# lumy.net
KiCad netlist of a schematic drawn in EAGLE
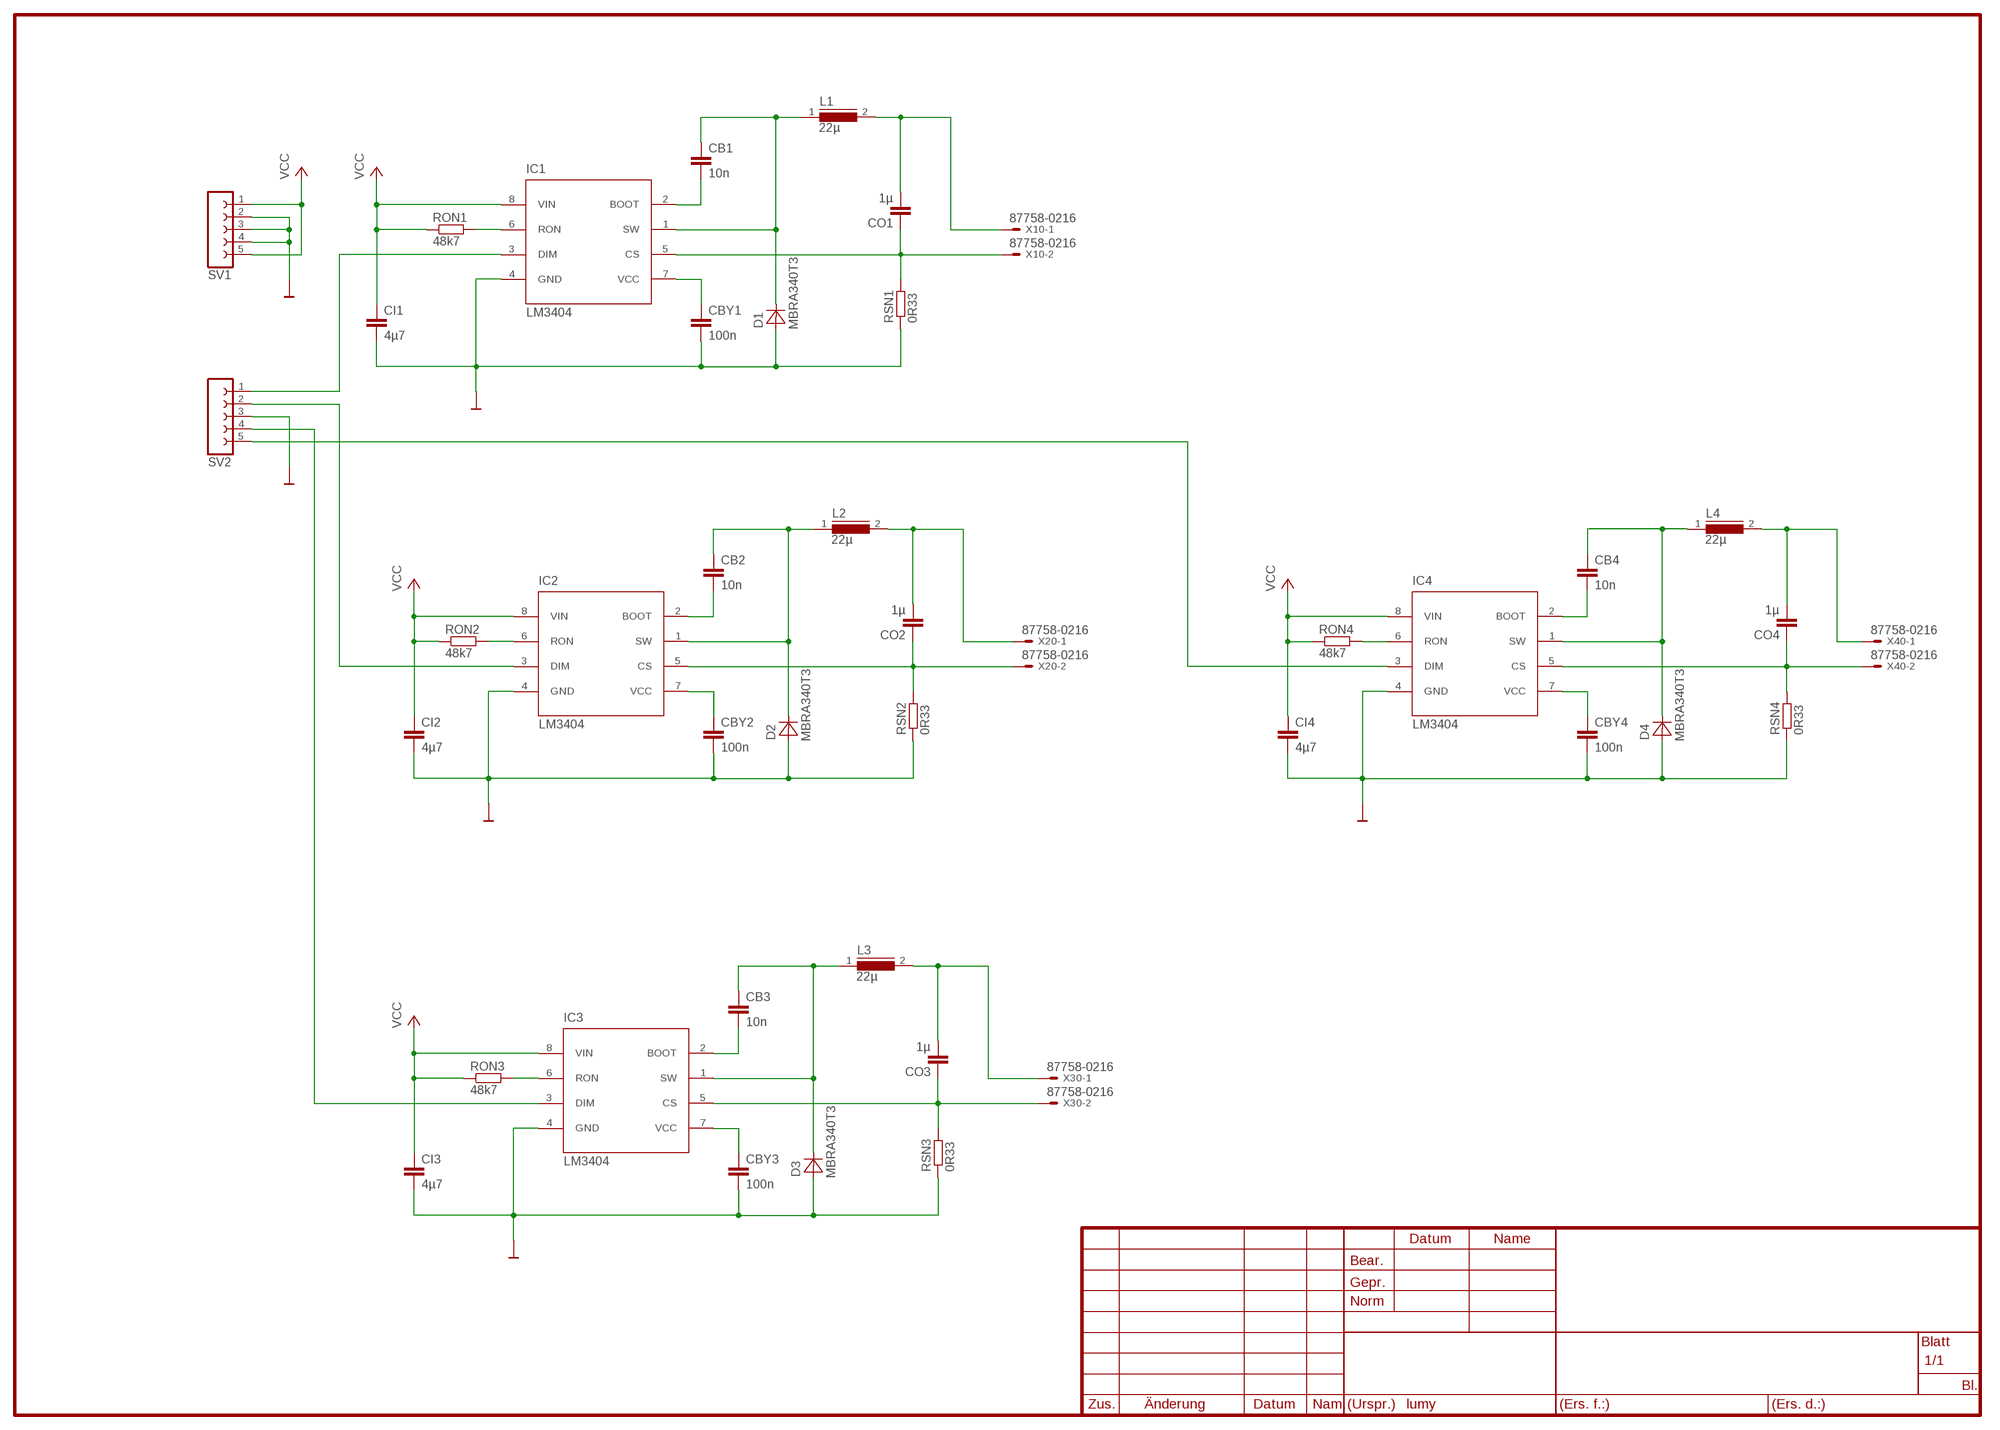
[diagram p0: schematic, sheet 1]

(export (version "E")
  (design (tool "Eeschema 10.0.6"))
  (components
    (comp (ref "CB1")
      (value "10n")
      (footprint "eagle-import:C0603")
      (libsource (lib "eagle-import") (part "C-EUC0603"))
    )
    (comp (ref "CB2")
      (value "10n")
      (footprint "eagle-import:C0603")
      (libsource (lib "eagle-import") (part "C-EUC0603"))
    )
    (comp (ref "CB3")
      (value "10n")
      (footprint "eagle-import:C0603")
      (libsource (lib "eagle-import") (part "C-EUC0603"))
    )
    (comp (ref "CB4")
      (value "10n")
      (footprint "eagle-import:C0603")
      (libsource (lib "eagle-import") (part "C-EUC0603"))
    )
    (comp (ref "CBY1")
      (value "100n")
      (footprint "eagle-import:C0603")
      (libsource (lib "eagle-import") (part "C-EUC0603"))
    )
    (comp (ref "CBY2")
      (value "100n")
      (footprint "eagle-import:C0603")
      (libsource (lib "eagle-import") (part "C-EUC0603"))
    )
    (comp (ref "CBY3")
      (value "100n")
      (footprint "eagle-import:C0603")
      (libsource (lib "eagle-import") (part "C-EUC0603"))
    )
    (comp (ref "CBY4")
      (value "100n")
      (footprint "eagle-import:C0603")
      (libsource (lib "eagle-import") (part "C-EUC0603"))
    )
    (comp (ref "CI1")
      (value "4µ7")
      (footprint "eagle-import:C0603")
      (libsource (lib "eagle-import") (part "C-EUC0603"))
    )
    (comp (ref "CI2")
      (value "4µ7")
      (footprint "eagle-import:C0603")
      (libsource (lib "eagle-import") (part "C-EUC0603"))
    )
    (comp (ref "CI3")
      (value "4µ7")
      (footprint "eagle-import:C0603")
      (libsource (lib "eagle-import") (part "C-EUC0603"))
    )
    (comp (ref "CI4")
      (value "4µ7")
      (footprint "eagle-import:C0603")
      (libsource (lib "eagle-import") (part "C-EUC0603"))
    )
    (comp (ref "CO1")
      (value "1µ")
      (footprint "eagle-import:C1206")
      (libsource (lib "eagle-import") (part "C-EUC1206"))
    )
    (comp (ref "CO2")
      (value "1µ")
      (footprint "eagle-import:C1206")
      (libsource (lib "eagle-import") (part "C-EUC1206"))
    )
    (comp (ref "CO3")
      (value "1µ")
      (footprint "eagle-import:C1206")
      (libsource (lib "eagle-import") (part "C-EUC1206"))
    )
    (comp (ref "CO4")
      (value "1µ")
      (footprint "eagle-import:C1206")
      (libsource (lib "eagle-import") (part "C-EUC1206"))
    )
    (comp (ref "D1")
      (value "MBRA340T3")
      (footprint "eagle-import:SMA")
      (libsource (lib "eagle-import") (part "MBRA340T3"))
    )
    (comp (ref "D2")
      (value "MBRA340T3")
      (footprint "eagle-import:SMA")
      (libsource (lib "eagle-import") (part "MBRA340T3"))
    )
    (comp (ref "D3")
      (value "MBRA340T3")
      (footprint "eagle-import:SMA")
      (libsource (lib "eagle-import") (part "MBRA340T3"))
    )
    (comp (ref "D4")
      (value "MBRA340T3")
      (footprint "eagle-import:SMA")
      (libsource (lib "eagle-import") (part "MBRA340T3"))
    )
    (comp (ref "IC1")
      (value "LM3404")
      (footprint "eagle-import:SO08")
      (libsource (lib "eagle-import") (part "LM3404"))
    )
    (comp (ref "IC2")
      (value "LM3404")
      (footprint "eagle-import:SO08")
      (libsource (lib "eagle-import") (part "LM3404"))
    )
    (comp (ref "IC3")
      (value "LM3404")
      (footprint "eagle-import:SO08")
      (libsource (lib "eagle-import") (part "LM3404"))
    )
    (comp (ref "IC4")
      (value "LM3404")
      (footprint "eagle-import:SO08")
      (libsource (lib "eagle-import") (part "LM3404"))
    )
    (comp (ref "L1")
      (value "22µ")
      (footprint "eagle-import:DR73")
      (libsource (lib "eagle-import") (part "DR73"))
    )
    (comp (ref "L2")
      (value "22µ")
      (footprint "eagle-import:DR73")
      (libsource (lib "eagle-import") (part "DR73"))
    )
    (comp (ref "L3")
      (value "22µ")
      (footprint "eagle-import:DR73")
      (libsource (lib "eagle-import") (part "DR73"))
    )
    (comp (ref "L4")
      (value "22µ")
      (footprint "eagle-import:DR73")
      (libsource (lib "eagle-import") (part "DR73"))
    )
    (comp (ref "RON1")
      (value "48k7")
      (footprint "eagle-import:R0805")
      (libsource (lib "eagle-import") (part "R-EU_R0805"))
    )
    (comp (ref "RON2")
      (value "48k7")
      (footprint "eagle-import:R0805")
      (libsource (lib "eagle-import") (part "R-EU_R0805"))
    )
    (comp (ref "RON3")
      (value "48k7")
      (footprint "eagle-import:R0805")
      (libsource (lib "eagle-import") (part "R-EU_R0805"))
    )
    (comp (ref "RON4")
      (value "48k7")
      (footprint "eagle-import:R0805")
      (libsource (lib "eagle-import") (part "R-EU_R0805"))
    )
    (comp (ref "RSN1")
      (value "0R33")
      (footprint "eagle-import:R1206")
      (libsource (lib "eagle-import") (part "R-EU_R1206"))
    )
    (comp (ref "RSN2")
      (value "0R33")
      (footprint "eagle-import:R1206")
      (libsource (lib "eagle-import") (part "R-EU_R1206"))
    )
    (comp (ref "RSN3")
      (value "0R33")
      (footprint "eagle-import:R1206")
      (libsource (lib "eagle-import") (part "R-EU_R1206"))
    )
    (comp (ref "RSN4")
      (value "0R33")
      (footprint "eagle-import:R1206")
      (libsource (lib "eagle-import") (part "R-EU_R1206"))
    )
    (comp (ref "SV1")
      (value "FE05-1")
      (footprint "eagle-import:FE05-1")
      (libsource (lib "eagle-import") (part "FE05-1"))
    )
    (comp (ref "SV2")
      (value "FE05-1")
      (footprint "eagle-import:FE05-1")
      (libsource (lib "eagle-import") (part "FE05-1"))
    )
    (comp (ref "X10")
      (value "87758-0216")
      (footprint "eagle-import:87758-0216")
      (libsource (lib "eagle-import") (part "87758-0216"))
    )
    (comp (ref "X20")
      (value "87758-0216")
      (footprint "eagle-import:87758-0216")
      (libsource (lib "eagle-import") (part "87758-0216"))
    )
    (comp (ref "X30")
      (value "87758-0216")
      (footprint "eagle-import:87758-0216")
      (libsource (lib "eagle-import") (part "87758-0216"))
    )
    (comp (ref "X40")
      (value "87758-0216")
      (footprint "eagle-import:87758-0216")
      (fields
        (field (name "MPN") "87758-0216")
        (field (name "OC_FARNELL") "unknown")
        (field (name "OC_NEWARK") "94M1513")
      )
      (libsource (lib "eagle-import") (part "87758-0216"))
    )
  )
  (nets
    (net (code "1") (name "GND") (class "Default")
      (node (ref "CBY1") (pin "2") (pinfunction "2_2") (pintype "passive"))
      (node (ref "CBY2") (pin "2") (pinfunction "2_2") (pintype "passive"))
      (node (ref "CBY3") (pin "2") (pinfunction "2_2") (pintype "passive"))
      (node (ref "CBY4") (pin "2") (pinfunction "2_2") (pintype "passive"))
      (node (ref "CI1") (pin "2") (pinfunction "2_2") (pintype "passive"))
      (node (ref "CI2") (pin "2") (pinfunction "2_2") (pintype "passive"))
      (node (ref "CI3") (pin "2") (pinfunction "2_2") (pintype "passive"))
      (node (ref "CI4") (pin "2") (pinfunction "2_2") (pintype "passive"))
      (node (ref "D1") (pin "A") (pinfunction "A_A") (pintype "passive"))
      (node (ref "D2") (pin "A") (pinfunction "A_A") (pintype "passive"))
      (node (ref "D3") (pin "A") (pinfunction "A_A") (pintype "passive"))
      (node (ref "D4") (pin "A") (pinfunction "A_A") (pintype "passive"))
      (node (ref "IC1") (pin "4") (pinfunction "GND_4") (pintype "power_in"))
      (node (ref "IC2") (pin "4") (pinfunction "GND_4") (pintype "power_in"))
      (node (ref "IC3") (pin "4") (pinfunction "GND_4") (pintype "power_in"))
      (node (ref "IC4") (pin "4") (pinfunction "GND_4") (pintype "power_in"))
      (node (ref "RSN1") (pin "1") (pinfunction "1_1") (pintype "passive"))
      (node (ref "RSN2") (pin "1") (pinfunction "1_1") (pintype "passive"))
      (node (ref "RSN3") (pin "1") (pinfunction "1_1") (pintype "passive"))
      (node (ref "RSN4") (pin "1") (pinfunction "1_1") (pintype "passive"))
      (node (ref "SV1") (pin "2") (pinfunction "2_2") (pintype "passive"))
      (node (ref "SV1") (pin "3") (pinfunction "3_3") (pintype "passive"))
      (node (ref "SV1") (pin "4") (pinfunction "4_4") (pintype "passive"))
      (node (ref "SV2") (pin "3") (pinfunction "3_3") (pintype "passive"))
    )
    (net (code "2") (name "Net-(IC1-BOOT)") (class "Default")
      (node (ref "CB1") (pin "2") (pinfunction "2_2") (pintype "passive"))
      (node (ref "IC1") (pin "2") (pinfunction "BOOT_2") (pintype "output"))
    )
    (net (code "3") (name "Net-(IC1-CS)") (class "Default")
      (node (ref "CO1") (pin "1") (pinfunction "1_1") (pintype "passive"))
      (node (ref "IC1") (pin "5") (pinfunction "CS_5") (pintype "input"))
      (node (ref "RSN1") (pin "2") (pinfunction "2_2") (pintype "passive"))
      (node (ref "X10") (pin "2") (pinfunction "S_2") (pintype "passive"))
    )
    (net (code "4") (name "Net-(IC1-DIM)") (class "Default")
      (node (ref "IC1") (pin "3") (pinfunction "DIM_3") (pintype "input"))
      (node (ref "SV2") (pin "1") (pinfunction "1_1") (pintype "passive"))
    )
    (net (code "5") (name "Net-(IC1-RON)") (class "Default")
      (node (ref "IC1") (pin "6") (pinfunction "RON_6") (pintype "input"))
      (node (ref "RON1") (pin "2") (pinfunction "2_2") (pintype "passive"))
    )
    (net (code "6") (name "Net-(IC1-SW)") (class "Default")
      (node (ref "CB1") (pin "1") (pinfunction "1_1") (pintype "passive"))
      (node (ref "D1") (pin "C") (pinfunction "C_C") (pintype "passive"))
      (node (ref "IC1") (pin "1") (pinfunction "SW_1") (pintype "output"))
      (node (ref "L1") (pin "1") (pinfunction "1_1") (pintype "passive"))
    )
    (net (code "7") (name "Net-(IC1-VCC)") (class "Default")
      (node (ref "CBY1") (pin "1") (pinfunction "1_1") (pintype "passive"))
      (node (ref "IC1") (pin "7") (pinfunction "VCC_7") (pintype "power_in"))
    )
    (net (code "8") (name "Net-(IC2-BOOT)") (class "Default")
      (node (ref "CB2") (pin "2") (pinfunction "2_2") (pintype "passive"))
      (node (ref "IC2") (pin "2") (pinfunction "BOOT_2") (pintype "output"))
    )
    (net (code "9") (name "Net-(IC2-CS)") (class "Default")
      (node (ref "CO2") (pin "1") (pinfunction "1_1") (pintype "passive"))
      (node (ref "IC2") (pin "5") (pinfunction "CS_5") (pintype "input"))
      (node (ref "RSN2") (pin "2") (pinfunction "2_2") (pintype "passive"))
      (node (ref "X20") (pin "2") (pinfunction "S_2") (pintype "passive"))
    )
    (net (code "10") (name "Net-(IC2-DIM)") (class "Default")
      (node (ref "IC2") (pin "3") (pinfunction "DIM_3") (pintype "input"))
      (node (ref "SV2") (pin "2") (pinfunction "2_2") (pintype "passive"))
    )
    (net (code "11") (name "Net-(IC2-RON)") (class "Default")
      (node (ref "IC2") (pin "6") (pinfunction "RON_6") (pintype "input"))
      (node (ref "RON2") (pin "2") (pinfunction "2_2") (pintype "passive"))
    )
    (net (code "12") (name "Net-(IC2-SW)") (class "Default")
      (node (ref "CB2") (pin "1") (pinfunction "1_1") (pintype "passive"))
      (node (ref "D2") (pin "C") (pinfunction "C_C") (pintype "passive"))
      (node (ref "IC2") (pin "1") (pinfunction "SW_1") (pintype "output"))
      (node (ref "L2") (pin "1") (pinfunction "1_1") (pintype "passive"))
    )
    (net (code "13") (name "Net-(IC2-VCC)") (class "Default")
      (node (ref "CBY2") (pin "1") (pinfunction "1_1") (pintype "passive"))
      (node (ref "IC2") (pin "7") (pinfunction "VCC_7") (pintype "power_in"))
    )
    (net (code "14") (name "Net-(IC3-BOOT)") (class "Default")
      (node (ref "CB3") (pin "2") (pinfunction "2_2") (pintype "passive"))
      (node (ref "IC3") (pin "2") (pinfunction "BOOT_2") (pintype "output"))
    )
    (net (code "15") (name "Net-(IC3-CS)") (class "Default")
      (node (ref "CO3") (pin "1") (pinfunction "1_1") (pintype "passive"))
      (node (ref "IC3") (pin "5") (pinfunction "CS_5") (pintype "input"))
      (node (ref "RSN3") (pin "2") (pinfunction "2_2") (pintype "passive"))
      (node (ref "X30") (pin "2") (pinfunction "S_2") (pintype "passive"))
    )
    (net (code "16") (name "Net-(IC3-DIM)") (class "Default")
      (node (ref "IC3") (pin "3") (pinfunction "DIM_3") (pintype "input"))
      (node (ref "SV2") (pin "4") (pinfunction "4_4") (pintype "passive"))
    )
    (net (code "17") (name "Net-(IC3-RON)") (class "Default")
      (node (ref "IC3") (pin "6") (pinfunction "RON_6") (pintype "input"))
      (node (ref "RON3") (pin "2") (pinfunction "2_2") (pintype "passive"))
    )
    (net (code "18") (name "Net-(IC3-SW)") (class "Default")
      (node (ref "CB3") (pin "1") (pinfunction "1_1") (pintype "passive"))
      (node (ref "D3") (pin "C") (pinfunction "C_C") (pintype "passive"))
      (node (ref "IC3") (pin "1") (pinfunction "SW_1") (pintype "output"))
      (node (ref "L3") (pin "1") (pinfunction "1_1") (pintype "passive"))
    )
    (net (code "19") (name "Net-(IC3-VCC)") (class "Default")
      (node (ref "CBY3") (pin "1") (pinfunction "1_1") (pintype "passive"))
      (node (ref "IC3") (pin "7") (pinfunction "VCC_7") (pintype "power_in"))
    )
    (net (code "20") (name "Net-(IC4-BOOT)") (class "Default")
      (node (ref "CB4") (pin "2") (pinfunction "2_2") (pintype "passive"))
      (node (ref "IC4") (pin "2") (pinfunction "BOOT_2") (pintype "output"))
    )
    (net (code "21") (name "Net-(IC4-CS)") (class "Default")
      (node (ref "CO4") (pin "1") (pinfunction "1_1") (pintype "passive"))
      (node (ref "IC4") (pin "5") (pinfunction "CS_5") (pintype "input"))
      (node (ref "RSN4") (pin "2") (pinfunction "2_2") (pintype "passive"))
      (node (ref "X40") (pin "2") (pinfunction "S_2") (pintype "passive"))
    )
    (net (code "22") (name "Net-(IC4-DIM)") (class "Default")
      (node (ref "IC4") (pin "3") (pinfunction "DIM_3") (pintype "input"))
      (node (ref "SV2") (pin "5") (pinfunction "5_5") (pintype "passive"))
    )
    (net (code "23") (name "Net-(IC4-RON)") (class "Default")
      (node (ref "IC4") (pin "6") (pinfunction "RON_6") (pintype "input"))
      (node (ref "RON4") (pin "2") (pinfunction "2_2") (pintype "passive"))
    )
    (net (code "24") (name "Net-(IC4-SW)") (class "Default")
      (node (ref "CB4") (pin "1") (pinfunction "1_1") (pintype "passive"))
      (node (ref "D4") (pin "C") (pinfunction "C_C") (pintype "passive"))
      (node (ref "IC4") (pin "1") (pinfunction "SW_1") (pintype "output"))
      (node (ref "L4") (pin "1") (pinfunction "1_1") (pintype "passive"))
    )
    (net (code "25") (name "Net-(IC4-VCC)") (class "Default")
      (node (ref "CBY4") (pin "1") (pinfunction "1_1") (pintype "passive"))
      (node (ref "IC4") (pin "7") (pinfunction "VCC_7") (pintype "power_in"))
    )
    (net (code "26") (name "Net-(X10A-S)") (class "Default")
      (node (ref "CO1") (pin "2") (pinfunction "2_2") (pintype "passive"))
      (node (ref "L1") (pin "2") (pinfunction "2_2") (pintype "passive"))
      (node (ref "X10") (pin "1") (pinfunction "S_1") (pintype "passive"))
    )
    (net (code "27") (name "Net-(X20A-S)") (class "Default")
      (node (ref "CO2") (pin "2") (pinfunction "2_2") (pintype "passive"))
      (node (ref "L2") (pin "2") (pinfunction "2_2") (pintype "passive"))
      (node (ref "X20") (pin "1") (pinfunction "S_1") (pintype "passive"))
    )
    (net (code "28") (name "Net-(X30A-S)") (class "Default")
      (node (ref "CO3") (pin "2") (pinfunction "2_2") (pintype "passive"))
      (node (ref "L3") (pin "2") (pinfunction "2_2") (pintype "passive"))
      (node (ref "X30") (pin "1") (pinfunction "S_1") (pintype "passive"))
    )
    (net (code "29") (name "Net-(X40A-S)") (class "Default")
      (node (ref "CO4") (pin "2") (pinfunction "2_2") (pintype "passive"))
      (node (ref "L4") (pin "2") (pinfunction "2_2") (pintype "passive"))
      (node (ref "X40") (pin "1") (pinfunction "S_1") (pintype "passive"))
    )
    (net (code "30") (name "VCC") (class "Default")
      (node (ref "CI1") (pin "1") (pinfunction "1_1") (pintype "passive"))
      (node (ref "CI2") (pin "1") (pinfunction "1_1") (pintype "passive"))
      (node (ref "CI3") (pin "1") (pinfunction "1_1") (pintype "passive"))
      (node (ref "CI4") (pin "1") (pinfunction "1_1") (pintype "passive"))
      (node (ref "IC1") (pin "8") (pinfunction "VIN_8") (pintype "input"))
      (node (ref "IC2") (pin "8") (pinfunction "VIN_8") (pintype "input"))
      (node (ref "IC3") (pin "8") (pinfunction "VIN_8") (pintype "input"))
      (node (ref "IC4") (pin "8") (pinfunction "VIN_8") (pintype "input"))
      (node (ref "RON1") (pin "1") (pinfunction "1_1") (pintype "passive"))
      (node (ref "RON2") (pin "1") (pinfunction "1_1") (pintype "passive"))
      (node (ref "RON3") (pin "1") (pinfunction "1_1") (pintype "passive"))
      (node (ref "RON4") (pin "1") (pinfunction "1_1") (pintype "passive"))
      (node (ref "SV1") (pin "1") (pinfunction "1_1") (pintype "passive"))
      (node (ref "SV1") (pin "5") (pinfunction "5_5") (pintype "passive"))
    )
  )
)
